# openSX70-bench.net
KiCad netlist of a schematic drawn in EAGLE
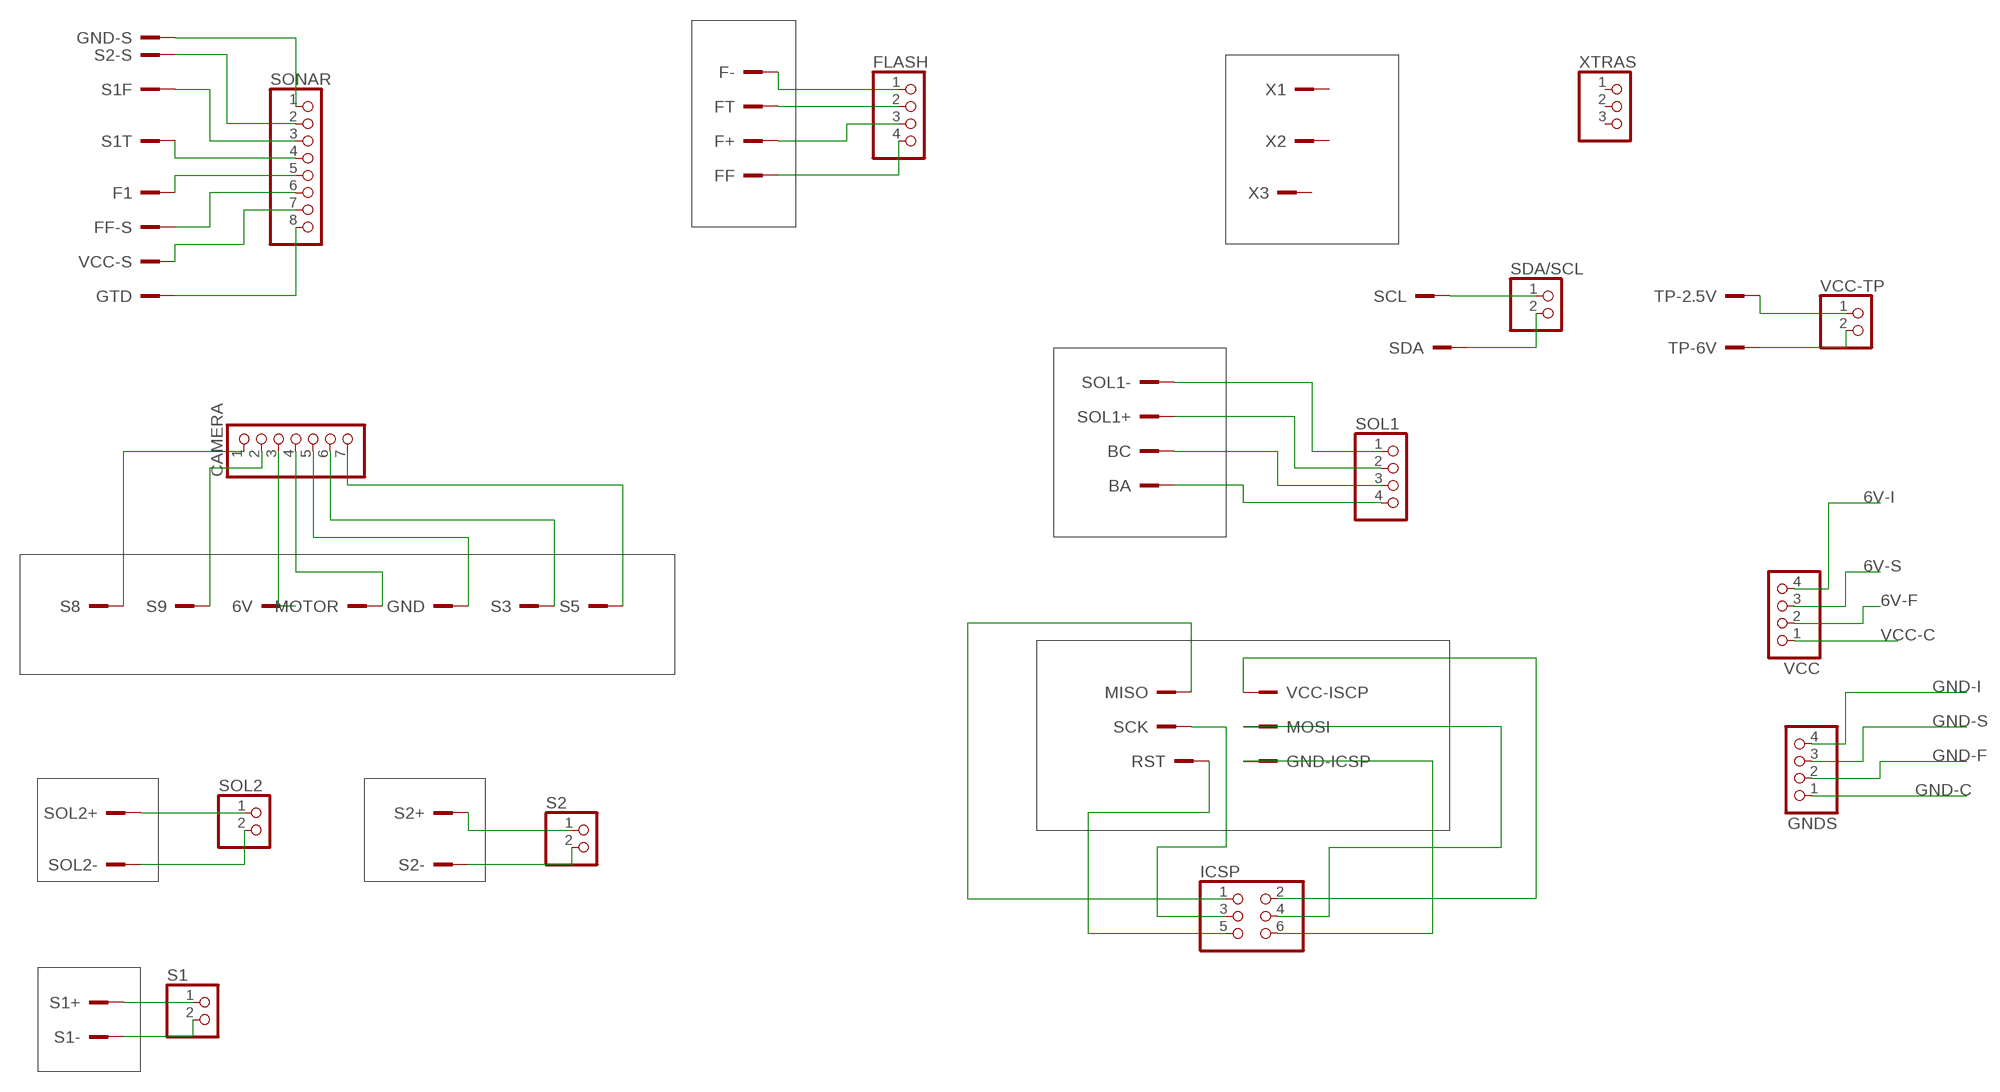
[diagram p0: schematic, sheet 1]

(export (version "E")
  (design (tool "Eeschema 10.0.6"))
  (components
    (comp (ref "6V")
      (value "PINHEAD")
      (footprint "eagle-import:1X01")
      (libsource (lib "eagle-import") (part "PINHEAD"))
    )
    (comp (ref "BA")
      (value "PINHEAD")
      (footprint "eagle-import:1X01")
      (libsource (lib "eagle-import") (part "PINHEAD"))
    )
    (comp (ref "BC")
      (value "PINHEAD")
      (footprint "eagle-import:1X01")
      (libsource (lib "eagle-import") (part "PINHEAD"))
    )
    (comp (ref "CAMERA")
      (value "PINHD-1X7")
      (footprint "eagle-import:1X07")
      (libsource (lib "eagle-import") (part "PINHD-1X7"))
    )
    (comp (ref "F+")
      (value "PINHEAD")
      (footprint "eagle-import:1X01")
      (libsource (lib "eagle-import") (part "PINHEAD"))
    )
    (comp (ref "F-")
      (value "PINHEAD")
      (footprint "eagle-import:1X01")
      (libsource (lib "eagle-import") (part "PINHEAD"))
    )
    (comp (ref "F1")
      (value "PINHEAD")
      (footprint "eagle-import:1X01")
      (libsource (lib "eagle-import") (part "PINHEAD"))
    )
    (comp (ref "FF")
      (value "PINHEAD")
      (footprint "eagle-import:1X01")
      (libsource (lib "eagle-import") (part "PINHEAD"))
    )
    (comp (ref "FF-S")
      (value "PINHEAD")
      (footprint "eagle-import:1X01")
      (libsource (lib "eagle-import") (part "PINHEAD"))
    )
    (comp (ref "FLASH")
      (value "PINHD-1X4")
      (footprint "eagle-import:1X04")
      (libsource (lib "eagle-import") (part "PINHD-1X4"))
    )
    (comp (ref "FT")
      (value "PINHEAD")
      (footprint "eagle-import:1X01")
      (libsource (lib "eagle-import") (part "PINHEAD"))
    )
    (comp (ref "GND")
      (value "PINHEAD")
      (footprint "eagle-import:1X01")
      (libsource (lib "eagle-import") (part "PINHEAD"))
    )
    (comp (ref "GND-ICSP")
      (value "PINHEAD")
      (footprint "eagle-import:1X01")
      (libsource (lib "eagle-import") (part "PINHEAD"))
    )
    (comp (ref "GND-S")
      (value "PINHEAD")
      (footprint "eagle-import:1X01")
      (libsource (lib "eagle-import") (part "PINHEAD"))
    )
    (comp (ref "GNDS")
      (value "PINHD-1X4")
      (footprint "eagle-import:1X04")
      (libsource (lib "eagle-import") (part "PINHD-1X4"))
    )
    (comp (ref "GTD")
      (value "PINHEAD")
      (footprint "eagle-import:1X01")
      (libsource (lib "eagle-import") (part "PINHEAD"))
    )
    (comp (ref "ICSP")
      (value "PINHD-2X3")
      (footprint "eagle-import:2X03")
      (libsource (lib "eagle-import") (part "PINHD-2X3"))
    )
    (comp (ref "MISO")
      (value "PINHEAD")
      (footprint "eagle-import:1X01")
      (libsource (lib "eagle-import") (part "PINHEAD"))
    )
    (comp (ref "MOSI")
      (value "PINHEAD")
      (footprint "eagle-import:1X01")
      (libsource (lib "eagle-import") (part "PINHEAD"))
    )
    (comp (ref "MOTOR")
      (value "PINHEAD")
      (footprint "eagle-import:1X01")
      (libsource (lib "eagle-import") (part "PINHEAD"))
    )
    (comp (ref "RST")
      (value "PINHEAD")
      (footprint "eagle-import:1X01")
      (libsource (lib "eagle-import") (part "PINHEAD"))
    )
    (comp (ref "S1")
      (value "PINHD-1X2")
      (footprint "eagle-import:1X02")
      (libsource (lib "eagle-import") (part "PINHD-1X2"))
    )
    (comp (ref "S1+")
      (value "PINHEAD")
      (footprint "eagle-import:1X01")
      (libsource (lib "eagle-import") (part "PINHEAD"))
    )
    (comp (ref "S1-")
      (value "PINHEAD")
      (footprint "eagle-import:1X01")
      (libsource (lib "eagle-import") (part "PINHEAD"))
    )
    (comp (ref "S1F")
      (value "PINHEAD")
      (footprint "eagle-import:1X01")
      (libsource (lib "eagle-import") (part "PINHEAD"))
    )
    (comp (ref "S1T")
      (value "PINHEAD")
      (footprint "eagle-import:1X01")
      (libsource (lib "eagle-import") (part "PINHEAD"))
    )
    (comp (ref "S2")
      (value "PINHD-1X2")
      (footprint "eagle-import:1X02")
      (libsource (lib "eagle-import") (part "PINHD-1X2"))
    )
    (comp (ref "S2+")
      (value "PINHEAD")
      (footprint "eagle-import:1X01")
      (libsource (lib "eagle-import") (part "PINHEAD"))
    )
    (comp (ref "S2-")
      (value "PINHEAD")
      (footprint "eagle-import:1X01")
      (libsource (lib "eagle-import") (part "PINHEAD"))
    )
    (comp (ref "S2-S")
      (value "PINHEAD")
      (footprint "eagle-import:1X01")
      (libsource (lib "eagle-import") (part "PINHEAD"))
    )
    (comp (ref "S3")
      (value "PINHEAD")
      (footprint "eagle-import:1X01")
      (libsource (lib "eagle-import") (part "PINHEAD"))
    )
    (comp (ref "S5")
      (value "PINHEAD")
      (footprint "eagle-import:1X01")
      (libsource (lib "eagle-import") (part "PINHEAD"))
    )
    (comp (ref "S8")
      (value "PINHEAD")
      (footprint "eagle-import:1X01")
      (libsource (lib "eagle-import") (part "PINHEAD"))
    )
    (comp (ref "S9")
      (value "PINHEAD")
      (footprint "eagle-import:1X01")
      (libsource (lib "eagle-import") (part "PINHEAD"))
    )
    (comp (ref "SCK")
      (value "PINHEAD")
      (footprint "eagle-import:1X01")
      (libsource (lib "eagle-import") (part "PINHEAD"))
    )
    (comp (ref "SCL")
      (value "PINHEAD")
      (footprint "eagle-import:1X01")
      (libsource (lib "eagle-import") (part "PINHEAD"))
    )
    (comp (ref "SDA")
      (value "PINHEAD")
      (footprint "eagle-import:1X01")
      (libsource (lib "eagle-import") (part "PINHEAD"))
    )
    (comp (ref "SDA/SCL")
      (value "PINHD-1X2")
      (footprint "eagle-import:1X02")
      (libsource (lib "eagle-import") (part "PINHD-1X2"))
    )
    (comp (ref "SOL1")
      (value "PINHD-1X4")
      (footprint "eagle-import:1X04")
      (libsource (lib "eagle-import") (part "PINHD-1X4"))
    )
    (comp (ref "SOL1+")
      (value "PINHEAD")
      (footprint "eagle-import:1X01")
      (libsource (lib "eagle-import") (part "PINHEAD"))
    )
    (comp (ref "SOL1-")
      (value "PINHEAD")
      (footprint "eagle-import:1X01")
      (libsource (lib "eagle-import") (part "PINHEAD"))
    )
    (comp (ref "SOL2")
      (value "PINHD-1X2")
      (footprint "eagle-import:1X02")
      (libsource (lib "eagle-import") (part "PINHD-1X2"))
    )
    (comp (ref "SOL2+")
      (value "PINHEAD")
      (footprint "eagle-import:1X01")
      (libsource (lib "eagle-import") (part "PINHEAD"))
    )
    (comp (ref "SOL2-")
      (value "PINHEAD")
      (footprint "eagle-import:1X01")
      (libsource (lib "eagle-import") (part "PINHEAD"))
    )
    (comp (ref "SONAR")
      (value "PINHD-1X8")
      (footprint "eagle-import:1X08")
      (libsource (lib "eagle-import") (part "PINHD-1X8"))
    )
    (comp (ref "TP-2.5V")
      (value "PINHEAD")
      (footprint "eagle-import:1X01")
      (libsource (lib "eagle-import") (part "PINHEAD"))
    )
    (comp (ref "TP-6V")
      (value "PINHEAD")
      (footprint "eagle-import:1X01")
      (libsource (lib "eagle-import") (part "PINHEAD"))
    )
    (comp (ref "VCC")
      (value "PINHD-1X4")
      (footprint "eagle-import:1X04")
      (libsource (lib "eagle-import") (part "PINHD-1X4"))
    )
    (comp (ref "VCC-ISCP")
      (value "PINHEAD")
      (footprint "eagle-import:1X01")
      (libsource (lib "eagle-import") (part "PINHEAD"))
    )
    (comp (ref "VCC-S")
      (value "PINHEAD")
      (footprint "eagle-import:1X01")
      (libsource (lib "eagle-import") (part "PINHEAD"))
    )
    (comp (ref "VCC-TP")
      (value "PINHD-1X2")
      (footprint "eagle-import:1X02")
      (libsource (lib "eagle-import") (part "PINHD-1X2"))
    )
    (comp (ref "X1")
      (value "PINHEAD")
      (footprint "eagle-import:1X01")
      (libsource (lib "eagle-import") (part "PINHEAD"))
    )
    (comp (ref "X2")
      (value "PINHEAD")
      (footprint "eagle-import:1X01")
      (libsource (lib "eagle-import") (part "PINHEAD"))
    )
    (comp (ref "X3")
      (value "PINHEAD")
      (footprint "eagle-import:1X01")
      (libsource (lib "eagle-import") (part "PINHEAD"))
    )
    (comp (ref "XTRAS")
      (value "PINHD-1X3")
      (footprint "eagle-import:1X03")
      (libsource (lib "eagle-import") (part "PINHD-1X3"))
    )
  )
  (nets
    (net (code "1") (name "/6V-F") (class "Default")
      (node (ref "F+") (pin "1") (pinfunction "KL_1") (pintype "passive"))
      (node (ref "FLASH") (pin "3") (pinfunction "3_3") (pintype "passive"))
      (node (ref "VCC") (pin "2") (pinfunction "2_2") (pintype "passive"))
    )
    (net (code "2") (name "/6V-I") (class "Default")
      (node (ref "ICSP") (pin "2") (pinfunction "2_2") (pintype "passive"))
      (node (ref "VCC") (pin "4") (pinfunction "4_4") (pintype "passive"))
      (node (ref "VCC-ISCP") (pin "1") (pinfunction "KL_1") (pintype "passive"))
    )
    (net (code "3") (name "/6V-S") (class "Default")
      (node (ref "SONAR") (pin "7") (pinfunction "7_7") (pintype "passive"))
      (node (ref "VCC") (pin "3") (pinfunction "3_3") (pintype "passive"))
      (node (ref "VCC-S") (pin "1") (pinfunction "KL_1") (pintype "passive"))
    )
    (net (code "4") (name "/GND-C") (class "Default")
      (node (ref "CAMERA") (pin "5") (pinfunction "5_5") (pintype "passive"))
      (node (ref "GND") (pin "1") (pinfunction "KL_1") (pintype "passive"))
      (node (ref "GNDS") (pin "1") (pinfunction "1_1") (pintype "passive"))
    )
    (net (code "5") (name "/GND-F") (class "Default")
      (node (ref "F-") (pin "1") (pinfunction "KL_1") (pintype "passive"))
      (node (ref "FLASH") (pin "1") (pinfunction "1_1") (pintype "passive"))
      (node (ref "GNDS") (pin "2") (pinfunction "2_2") (pintype "passive"))
    )
    (net (code "6") (name "/GND-I") (class "Default")
      (node (ref "GND-ICSP") (pin "1") (pinfunction "KL_1") (pintype "passive"))
      (node (ref "GNDS") (pin "4") (pinfunction "4_4") (pintype "passive"))
      (node (ref "ICSP") (pin "6") (pinfunction "6_6") (pintype "passive"))
    )
    (net (code "7") (name "/GND-S") (class "Default")
      (node (ref "GND-S") (pin "1") (pinfunction "KL_1") (pintype "passive"))
      (node (ref "GNDS") (pin "3") (pinfunction "3_3") (pintype "passive"))
      (node (ref "SONAR") (pin "1") (pinfunction "1_1") (pintype "passive"))
    )
    (net (code "8") (name "/VCC-C") (class "Default")
      (node (ref "6V") (pin "1") (pinfunction "KL_1") (pintype "passive"))
      (node (ref "CAMERA") (pin "3") (pinfunction "3_3") (pintype "passive"))
      (node (ref "VCC") (pin "1") (pinfunction "1_1") (pintype "passive"))
    )
    (net (code "9") (name "Net-(BA-KL)") (class "Default")
      (node (ref "BA") (pin "1") (pinfunction "KL_1") (pintype "passive"))
      (node (ref "SOL1") (pin "4") (pinfunction "4_4") (pintype "passive"))
    )
    (net (code "10") (name "Net-(BC-KL)") (class "Default")
      (node (ref "BC") (pin "1") (pinfunction "KL_1") (pintype "passive"))
      (node (ref "SOL1") (pin "3") (pinfunction "3_3") (pintype "passive"))
    )
    (net (code "11") (name "Net-(F1-KL)") (class "Default")
      (node (ref "F1") (pin "1") (pinfunction "KL_1") (pintype "passive"))
      (node (ref "SONAR") (pin "5") (pinfunction "5_5") (pintype "passive"))
    )
    (net (code "12") (name "Net-(FF-KL)") (class "Default")
      (node (ref "FF") (pin "1") (pinfunction "KL_1") (pintype "passive"))
      (node (ref "FLASH") (pin "4") (pinfunction "4_4") (pintype "passive"))
    )
    (net (code "13") (name "Net-(FF-S-KL)") (class "Default")
      (node (ref "FF-S") (pin "1") (pinfunction "KL_1") (pintype "passive"))
      (node (ref "SONAR") (pin "6") (pinfunction "6_6") (pintype "passive"))
    )
    (net (code "14") (name "Net-(FT-KL)") (class "Default")
      (node (ref "FLASH") (pin "2") (pinfunction "2_2") (pintype "passive"))
      (node (ref "FT") (pin "1") (pinfunction "KL_1") (pintype "passive"))
    )
    (net (code "15") (name "Net-(GTD-KL)") (class "Default")
      (node (ref "GTD") (pin "1") (pinfunction "KL_1") (pintype "passive"))
      (node (ref "SONAR") (pin "8") (pinfunction "8_8") (pintype "passive"))
    )
    (net (code "16") (name "Net-(MISO-KL)") (class "Default")
      (node (ref "ICSP") (pin "1") (pinfunction "1_1") (pintype "passive"))
      (node (ref "MISO") (pin "1") (pinfunction "KL_1") (pintype "passive"))
    )
    (net (code "17") (name "Net-(MOSI-KL)") (class "Default")
      (node (ref "ICSP") (pin "4") (pinfunction "4_4") (pintype "passive"))
      (node (ref "MOSI") (pin "1") (pinfunction "KL_1") (pintype "passive"))
    )
    (net (code "18") (name "Net-(MOTOR-KL)") (class "Default")
      (node (ref "CAMERA") (pin "4") (pinfunction "4_4") (pintype "passive"))
      (node (ref "MOTOR") (pin "1") (pinfunction "KL_1") (pintype "passive"))
    )
    (net (code "19") (name "Net-(RST-KL)") (class "Default")
      (node (ref "ICSP") (pin "5") (pinfunction "5_5") (pintype "passive"))
      (node (ref "RST") (pin "1") (pinfunction "KL_1") (pintype "passive"))
    )
    (net (code "20") (name "Net-(S1+-KL)") (class "Default")
      (node (ref "S1") (pin "1") (pinfunction "1_1") (pintype "passive"))
      (node (ref "S1+") (pin "1") (pinfunction "KL_1") (pintype "passive"))
    )
    (net (code "21") (name "Net-(S1--KL)") (class "Default")
      (node (ref "S1") (pin "2") (pinfunction "2_2") (pintype "passive"))
      (node (ref "S1-") (pin "1") (pinfunction "KL_1") (pintype "passive"))
    )
    (net (code "22") (name "Net-(S1F-KL)") (class "Default")
      (node (ref "S1F") (pin "1") (pinfunction "KL_1") (pintype "passive"))
      (node (ref "SONAR") (pin "3") (pinfunction "3_3") (pintype "passive"))
    )
    (net (code "23") (name "Net-(S1T-KL)") (class "Default")
      (node (ref "S1T") (pin "1") (pinfunction "KL_1") (pintype "passive"))
      (node (ref "SONAR") (pin "4") (pinfunction "4_4") (pintype "passive"))
    )
    (net (code "24") (name "Net-(S2+-KL)") (class "Default")
      (node (ref "S2") (pin "1") (pinfunction "1_1") (pintype "passive"))
      (node (ref "S2+") (pin "1") (pinfunction "KL_1") (pintype "passive"))
    )
    (net (code "25") (name "Net-(S2--KL)") (class "Default")
      (node (ref "S2") (pin "2") (pinfunction "2_2") (pintype "passive"))
      (node (ref "S2-") (pin "1") (pinfunction "KL_1") (pintype "passive"))
    )
    (net (code "26") (name "Net-(S2-S-KL)") (class "Default")
      (node (ref "S2-S") (pin "1") (pinfunction "KL_1") (pintype "passive"))
      (node (ref "SONAR") (pin "2") (pinfunction "2_2") (pintype "passive"))
    )
    (net (code "27") (name "Net-(S3-KL)") (class "Default")
      (node (ref "CAMERA") (pin "6") (pinfunction "6_6") (pintype "passive"))
      (node (ref "S3") (pin "1") (pinfunction "KL_1") (pintype "passive"))
    )
    (net (code "28") (name "Net-(S5-KL)") (class "Default")
      (node (ref "CAMERA") (pin "7") (pinfunction "7_7") (pintype "passive"))
      (node (ref "S5") (pin "1") (pinfunction "KL_1") (pintype "passive"))
    )
    (net (code "29") (name "Net-(S8-KL)") (class "Default")
      (node (ref "CAMERA") (pin "1") (pinfunction "1_1") (pintype "passive"))
      (node (ref "S8") (pin "1") (pinfunction "KL_1") (pintype "passive"))
    )
    (net (code "30") (name "Net-(S9-KL)") (class "Default")
      (node (ref "CAMERA") (pin "2") (pinfunction "2_2") (pintype "passive"))
      (node (ref "S9") (pin "1") (pinfunction "KL_1") (pintype "passive"))
    )
    (net (code "31") (name "Net-(SCK-KL)") (class "Default")
      (node (ref "ICSP") (pin "3") (pinfunction "3_3") (pintype "passive"))
      (node (ref "SCK") (pin "1") (pinfunction "KL_1") (pintype "passive"))
    )
    (net (code "32") (name "Net-(SCL-KL)") (class "Default")
      (node (ref "SCL") (pin "1") (pinfunction "KL_1") (pintype "passive"))
      (node (ref "SDA/SCL") (pin "1") (pinfunction "1_1") (pintype "passive"))
    )
    (net (code "33") (name "Net-(SDA-KL)") (class "Default")
      (node (ref "SDA") (pin "1") (pinfunction "KL_1") (pintype "passive"))
      (node (ref "SDA/SCL") (pin "2") (pinfunction "2_2") (pintype "passive"))
    )
    (net (code "34") (name "Net-(SOL1+-KL)") (class "Default")
      (node (ref "SOL1") (pin "2") (pinfunction "2_2") (pintype "passive"))
      (node (ref "SOL1+") (pin "1") (pinfunction "KL_1") (pintype "passive"))
    )
    (net (code "35") (name "Net-(SOL1--KL)") (class "Default")
      (node (ref "SOL1") (pin "1") (pinfunction "1_1") (pintype "passive"))
      (node (ref "SOL1-") (pin "1") (pinfunction "KL_1") (pintype "passive"))
    )
    (net (code "36") (name "Net-(SOL2+-KL)") (class "Default")
      (node (ref "SOL2") (pin "1") (pinfunction "1_1") (pintype "passive"))
      (node (ref "SOL2+") (pin "1") (pinfunction "KL_1") (pintype "passive"))
    )
    (net (code "37") (name "Net-(SOL2--KL)") (class "Default")
      (node (ref "SOL2") (pin "2") (pinfunction "2_2") (pintype "passive"))
      (node (ref "SOL2-") (pin "1") (pinfunction "KL_1") (pintype "passive"))
    )
    (net (code "38") (name "Net-(TP-2.5V-KL)") (class "Default")
      (node (ref "TP-2.5V") (pin "1") (pinfunction "KL_1") (pintype "passive"))
      (node (ref "VCC-TP") (pin "1") (pinfunction "1_1") (pintype "passive"))
    )
    (net (code "39") (name "Net-(TP-6V-KL)") (class "Default")
      (node (ref "TP-6V") (pin "1") (pinfunction "KL_1") (pintype "passive"))
      (node (ref "VCC-TP") (pin "2") (pinfunction "2_2") (pintype "passive"))
    )
    (net (code "40") (name "unconnected-(X1-KL-Pad1)") (class "Default")
      (node (ref "X1") (pin "1") (pinfunction "KL_1") (pintype "passive"))
    )
    (net (code "41") (name "unconnected-(X2-KL-Pad1)") (class "Default")
      (node (ref "X2") (pin "1") (pinfunction "KL_1") (pintype "passive"))
    )
    (net (code "42") (name "unconnected-(X3-KL-Pad1)") (class "Default")
      (node (ref "X3") (pin "1") (pinfunction "KL_1") (pintype "passive"))
    )
    (net (code "43") (name "unconnected-(XTRAS-Pad1)") (class "Default")
      (node (ref "XTRAS") (pin "1") (pinfunction "1_1") (pintype "passive"))
    )
    (net (code "44") (name "unconnected-(XTRAS-Pad2)") (class "Default")
      (node (ref "XTRAS") (pin "2") (pinfunction "2_2") (pintype "passive"))
    )
    (net (code "45") (name "unconnected-(XTRAS-Pad3)") (class "Default")
      (node (ref "XTRAS") (pin "3") (pinfunction "3_3") (pintype "passive"))
    )
  )
)
